# lifi_1.net
KiCad netlist of a schematic drawn in EAGLE
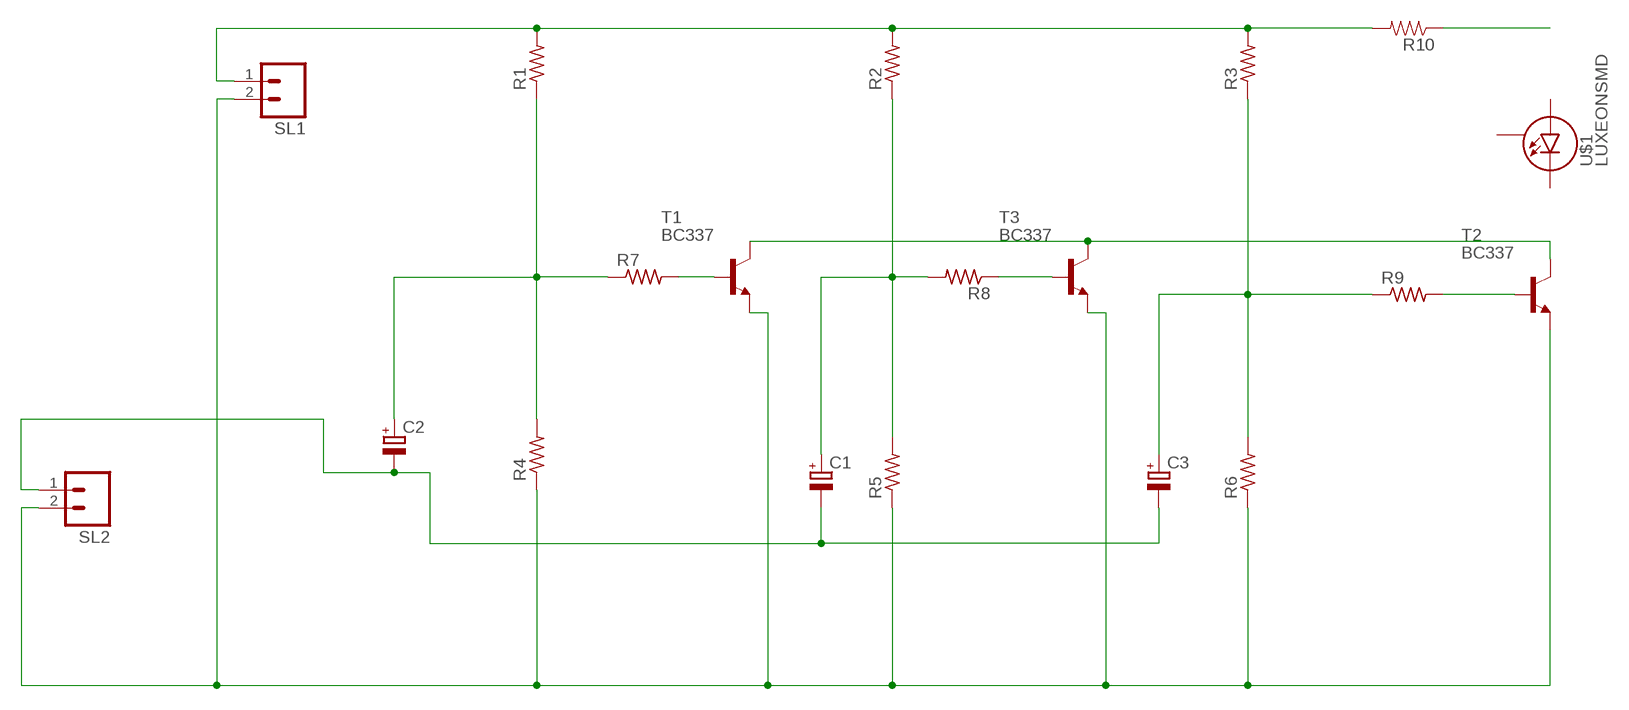
[diagram p0: schematic, sheet 1]

(export (version "E")
  (design (tool "Eeschema 10.0.6"))
  (components
    (comp (ref "C1")
      (value "CPOL-EUE2,5-6E")
      (footprint "eagle-import:E2,5-6E")
      (libsource (lib "eagle-import") (part "CPOL-EUE2,5-6E"))
    )
    (comp (ref "C2")
      (value "CPOL-EUE2,5-6E")
      (footprint "eagle-import:E2,5-6E")
      (libsource (lib "eagle-import") (part "CPOL-EUE2,5-6E"))
    )
    (comp (ref "C3")
      (value "CPOL-EUE2,5-6E")
      (footprint "eagle-import:E2,5-6E")
      (libsource (lib "eagle-import") (part "CPOL-EUE2,5-6E"))
    )
    (comp (ref "R1")
      (value "RESISTOR0207/7")
      (footprint "eagle-import:0207_7")
      (libsource (lib "eagle-import") (part "RESISTOR0207/7"))
    )
    (comp (ref "R2")
      (value "RESISTOR0207/7")
      (footprint "eagle-import:0207_7")
      (libsource (lib "eagle-import") (part "RESISTOR0207/7"))
    )
    (comp (ref "R3")
      (value "RESISTOR0207/7")
      (footprint "eagle-import:0207_7")
      (libsource (lib "eagle-import") (part "RESISTOR0207/7"))
    )
    (comp (ref "R4")
      (value "RESISTOR0207/7")
      (footprint "eagle-import:0207_7")
      (libsource (lib "eagle-import") (part "RESISTOR0207/7"))
    )
    (comp (ref "R5")
      (value "RESISTOR0207/7")
      (footprint "eagle-import:0207_7")
      (libsource (lib "eagle-import") (part "RESISTOR0207/7"))
    )
    (comp (ref "R6")
      (value "RESISTOR0207/7")
      (footprint "eagle-import:0207_7")
      (libsource (lib "eagle-import") (part "RESISTOR0207/7"))
    )
    (comp (ref "R7")
      (value "RESISTOR0207/7")
      (footprint "eagle-import:0207_7")
      (libsource (lib "eagle-import") (part "RESISTOR0207/7"))
    )
    (comp (ref "R8")
      (value "RESISTOR0207/7")
      (footprint "eagle-import:0207_7")
      (libsource (lib "eagle-import") (part "RESISTOR0207/7"))
    )
    (comp (ref "R9")
      (value "RESISTOR0207/7")
      (footprint "eagle-import:0207_7")
      (libsource (lib "eagle-import") (part "RESISTOR0207/7"))
    )
    (comp (ref "R10")
      (value "RESISTORPTH-1W")
      (footprint "eagle-import:AXIAL-0.6")
      (libsource (lib "eagle-import") (part "RESISTORPTH-1W"))
    )
    (comp (ref "SL1")
      (value "M02")
      (footprint "eagle-import:02P")
      (libsource (lib "eagle-import") (part "M02"))
    )
    (comp (ref "SL2")
      (value "M02")
      (footprint "eagle-import:02P")
      (libsource (lib "eagle-import") (part "con-amp-quick_M02"))
    )
    (comp (ref "T1")
      (value "BC337")
      (footprint "eagle-import:TO92")
      (libsource (lib "eagle-import") (part "BC337"))
    )
    (comp (ref "T2")
      (value "BC337")
      (footprint "eagle-import:TO92")
      (libsource (lib "eagle-import") (part "BC337"))
    )
    (comp (ref "T3")
      (value "BC337")
      (footprint "eagle-import:TO92")
      (libsource (lib "eagle-import") (part "BC337"))
    )
    (comp (ref "U$1")
      (value "LUXEONSMD")
      (footprint "eagle-import:LUXEON")
      (libsource (lib "eagle-import") (part "LUXEONSMD"))
    )
  )
  (nets
    (net (code "1") (name "Net-(C1-Pad+)") (class "Default")
      (node (ref "C1") (pin "+") (pinfunction "+_+") (pintype "passive"))
      (node (ref "R2") (pin "1") (pinfunction "1_1") (pintype "passive"))
      (node (ref "R5") (pin "2") (pinfunction "2_2") (pintype "passive"))
      (node (ref "R8") (pin "2") (pinfunction "2_2") (pintype "passive"))
    )
    (net (code "2") (name "Net-(C1-Pad-)") (class "Default")
      (node (ref "C1") (pin "-") (pinfunction "-_-") (pintype "passive"))
      (node (ref "C2") (pin "-") (pinfunction "-_-") (pintype "passive"))
      (node (ref "C3") (pin "-") (pinfunction "-_-") (pintype "passive"))
      (node (ref "SL2") (pin "1") (pinfunction "1_1") (pintype "passive"))
    )
    (net (code "3") (name "Net-(C2-Pad+)") (class "Default")
      (node (ref "C2") (pin "+") (pinfunction "+_+") (pintype "passive"))
      (node (ref "R1") (pin "1") (pinfunction "1_1") (pintype "passive"))
      (node (ref "R4") (pin "2") (pinfunction "2_2") (pintype "passive"))
      (node (ref "R7") (pin "1") (pinfunction "1_1") (pintype "passive"))
    )
    (net (code "4") (name "Net-(C3-Pad+)") (class "Default")
      (node (ref "C3") (pin "+") (pinfunction "+_+") (pintype "passive"))
      (node (ref "R3") (pin "1") (pinfunction "1_1") (pintype "passive"))
      (node (ref "R6") (pin "2") (pinfunction "2_2") (pintype "passive"))
      (node (ref "R9") (pin "1") (pinfunction "1_1") (pintype "passive"))
    )
    (net (code "5") (name "Net-(R10-2)") (class "Default")
      (node (ref "R1") (pin "2") (pinfunction "2_2") (pintype "passive"))
      (node (ref "R10") (pin "P$2") (pinfunction "2_P$2") (pintype "passive"))
      (node (ref "R2") (pin "2") (pinfunction "2_2") (pintype "passive"))
      (node (ref "R3") (pin "2") (pinfunction "2_2") (pintype "passive"))
      (node (ref "SL1") (pin "1") (pinfunction "1_1") (pintype "passive"))
    )
    (net (code "6") (name "Net-(T1-B)") (class "Default")
      (node (ref "R7") (pin "2") (pinfunction "2_2") (pintype "passive"))
      (node (ref "T1") (pin "2") (pinfunction "B_2") (pintype "passive"))
    )
    (net (code "7") (name "Net-(T1-C)") (class "Default")
      (node (ref "T1") (pin "3") (pinfunction "C_3") (pintype "passive"))
      (node (ref "T2") (pin "3") (pinfunction "C_3") (pintype "passive"))
      (node (ref "T3") (pin "3") (pinfunction "C_3") (pintype "passive"))
    )
    (net (code "8") (name "Net-(T1-E)") (class "Default")
      (node (ref "R4") (pin "1") (pinfunction "1_1") (pintype "passive"))
      (node (ref "R5") (pin "1") (pinfunction "1_1") (pintype "passive"))
      (node (ref "R6") (pin "1") (pinfunction "1_1") (pintype "passive"))
      (node (ref "SL1") (pin "2") (pinfunction "2_2") (pintype "passive"))
      (node (ref "SL2") (pin "2") (pinfunction "2_2") (pintype "passive"))
      (node (ref "T1") (pin "1") (pinfunction "E_1") (pintype "passive"))
      (node (ref "T2") (pin "1") (pinfunction "E_1") (pintype "passive"))
      (node (ref "T3") (pin "1") (pinfunction "E_1") (pintype "passive"))
    )
    (net (code "9") (name "Net-(T2-B)") (class "Default")
      (node (ref "R9") (pin "2") (pinfunction "2_2") (pintype "passive"))
      (node (ref "T2") (pin "2") (pinfunction "B_2") (pintype "passive"))
    )
    (net (code "10") (name "Net-(T3-B)") (class "Default")
      (node (ref "R8") (pin "1") (pinfunction "1_1") (pintype "passive"))
      (node (ref "T3") (pin "2") (pinfunction "B_2") (pintype "passive"))
    )
    (net (code "11") (name "unconnected-(R10-1-PadP$1)") (class "Default")
      (node (ref "R10") (pin "P$1") (pinfunction "1_P$1") (pintype "passive"))
    )
    (net (code "12") (name "unconnected-(U$1-PadA)") (class "Default")
      (node (ref "U$1") (pin "A") (pinfunction "A_A") (pintype "passive"))
    )
    (net (code "13") (name "unconnected-(U$1-PadC)") (class "Default")
      (node (ref "U$1") (pin "C") (pinfunction "C_C") (pintype "passive"))
    )
    (net (code "14") (name "unconnected-(U$1-PadS)") (class "Default")
      (node (ref "U$1") (pin "S") (pinfunction "S_S") (pintype "bidirectional"))
    )
  )
)
